# Valve_transistors.net
KiCad netlist of a schematic drawn in Altium Designer
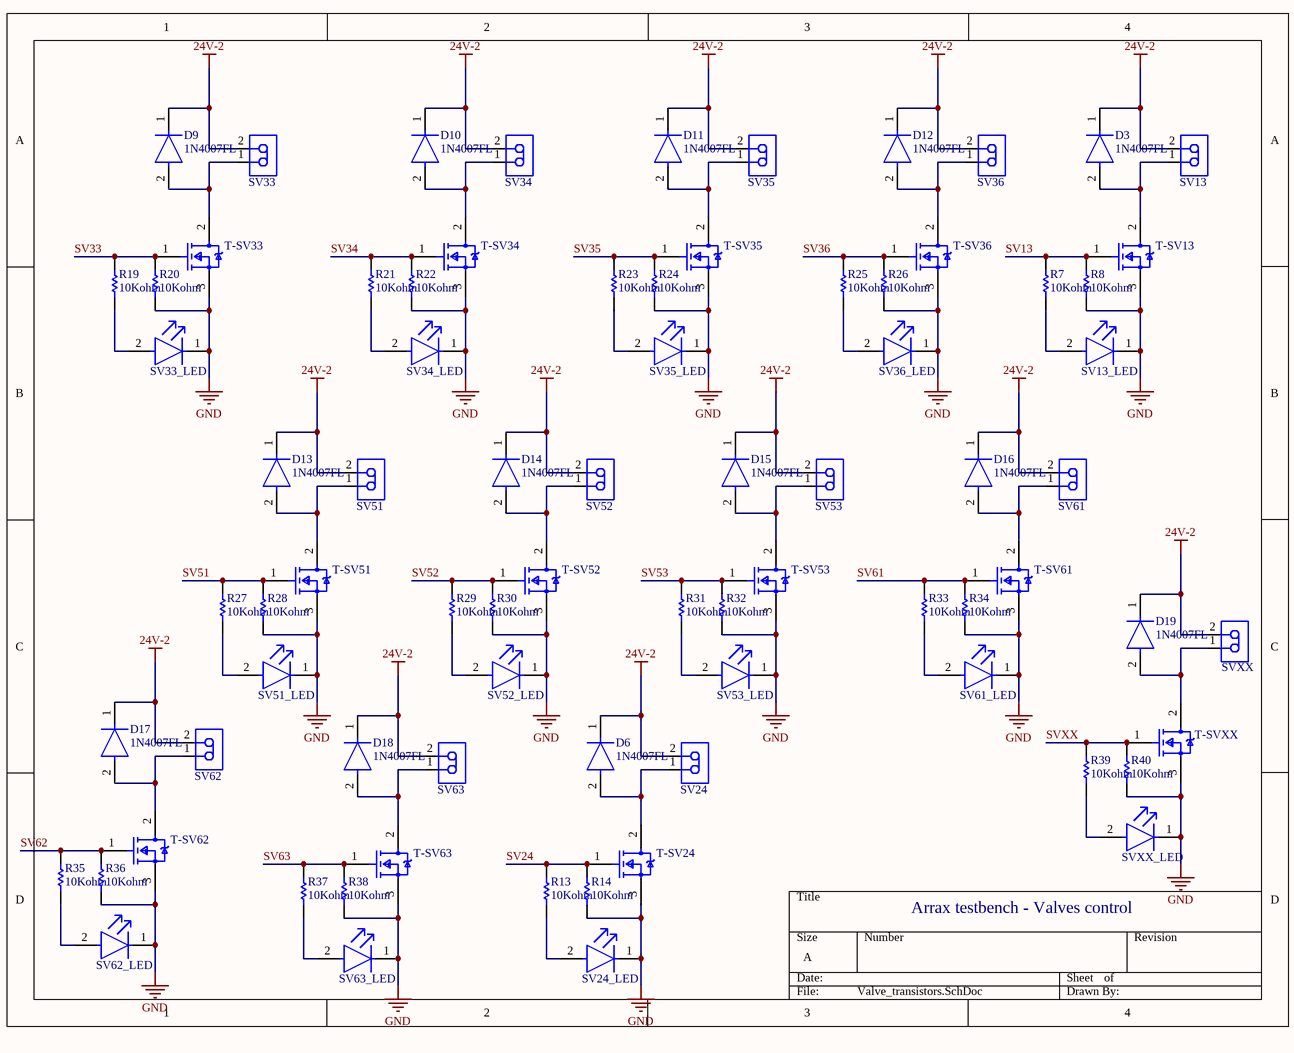
[diagram p0: Valve_transistors.SchDoc]

(export (version "E")
  (design (tool "Eeschema 10.0.6"))
  (components
    (comp (ref "D3")
      (value "1N4007FL")
      (footprint "FP-1N4007FL-MFG")
      (description "1N4007FL Diode Gen Purp 1KV 1A SOD123FL")
      (libsource (lib "Altium Content Vault") (part "d7152d700b627762746794eb795d46e"))
    )
    (comp (ref "D6")
      (value "1N4007FL")
      (footprint "FP-1N4007FL-MFG")
      (description "1N4007FL Diode Gen Purp 1KV 1A SOD123FL")
      (libsource (lib "Altium Content Vault") (part "d7152d700b627762746794eb795d46e"))
    )
    (comp (ref "D9")
      (value "1N4007FL")
      (footprint "FP-1N4007FL-MFG")
      (description "1N4007FL Diode Gen Purp 1KV 1A SOD123FL")
      (libsource (lib "Altium Content Vault") (part "d7152d700b627762746794eb795d46e"))
    )
    (comp (ref "D10")
      (value "1N4007FL")
      (footprint "FP-1N4007FL-MFG")
      (description "1N4007FL Diode Gen Purp 1KV 1A SOD123FL")
      (libsource (lib "Altium Content Vault") (part "d7152d700b627762746794eb795d46e"))
    )
    (comp (ref "D11")
      (value "1N4007FL")
      (footprint "FP-1N4007FL-MFG")
      (description "1N4007FL Diode Gen Purp 1KV 1A SOD123FL")
      (libsource (lib "Altium Content Vault") (part "d7152d700b627762746794eb795d46e"))
    )
    (comp (ref "D12")
      (value "1N4007FL")
      (footprint "FP-1N4007FL-MFG")
      (description "1N4007FL Diode Gen Purp 1KV 1A SOD123FL")
      (libsource (lib "Altium Content Vault") (part "d7152d700b627762746794eb795d46e"))
    )
    (comp (ref "D13")
      (value "1N4007FL")
      (footprint "FP-1N4007FL-MFG")
      (description "1N4007FL Diode Gen Purp 1KV 1A SOD123FL")
      (libsource (lib "Altium Content Vault") (part "d7152d700b627762746794eb795d46e"))
    )
    (comp (ref "D14")
      (value "1N4007FL")
      (footprint "FP-1N4007FL-MFG")
      (description "1N4007FL Diode Gen Purp 1KV 1A SOD123FL")
      (libsource (lib "Altium Content Vault") (part "d7152d700b627762746794eb795d46e"))
    )
    (comp (ref "D15")
      (value "1N4007FL")
      (footprint "FP-1N4007FL-MFG")
      (description "1N4007FL Diode Gen Purp 1KV 1A SOD123FL")
      (libsource (lib "Altium Content Vault") (part "d7152d700b627762746794eb795d46e"))
    )
    (comp (ref "D16")
      (value "1N4007FL")
      (footprint "FP-1N4007FL-MFG")
      (description "1N4007FL Diode Gen Purp 1KV 1A SOD123FL")
      (libsource (lib "Altium Content Vault") (part "d7152d700b627762746794eb795d46e"))
    )
    (comp (ref "D17")
      (value "1N4007FL")
      (footprint "FP-1N4007FL-MFG")
      (description "1N4007FL Diode Gen Purp 1KV 1A SOD123FL")
      (libsource (lib "Altium Content Vault") (part "d7152d700b627762746794eb795d46e"))
    )
    (comp (ref "D18")
      (value "1N4007FL")
      (footprint "FP-1N4007FL-MFG")
      (description "1N4007FL Diode Gen Purp 1KV 1A SOD123FL")
      (libsource (lib "Altium Content Vault") (part "d7152d700b627762746794eb795d46e"))
    )
    (comp (ref "D19")
      (value "1N4007FL")
      (footprint "FP-1N4007FL-MFG")
      (description "1N4007FL Diode Gen Purp 1KV 1A SOD123FL")
      (libsource (lib "Altium Content Vault") (part "d7152d700b627762746794eb795d46e"))
    )
    (comp (ref "R7")
      (value "10Kohm")
      (footprint "RESC2013X60X30NL20T20")
      (fields (field (name "MANUFACTURER") "KOA Speer") (field (name "PART NUMBER") "RK73H2ATTD1003F"))
      (libsource (lib "Altium Content Vault") (part "RES"))
    )
    (comp (ref "R8")
      (value "10Kohm")
      (footprint "RESC2013X60X30NL20T20")
      (fields (field (name "MANUFACTURER") "KOA Speer") (field (name "PART NUMBER") "RK73H2ATTD1003F"))
      (libsource (lib "Altium Content Vault") (part "RES"))
    )
    (comp (ref "R13")
      (value "10Kohm")
      (footprint "RESC2013X60X30NL20T20")
      (fields (field (name "MANUFACTURER") "KOA Speer") (field (name "PART NUMBER") "RK73H2ATTD1003F"))
      (libsource (lib "Altium Content Vault") (part "RES"))
    )
    (comp (ref "R14")
      (value "10Kohm")
      (footprint "RESC2013X60X30NL20T20")
      (fields (field (name "MANUFACTURER") "KOA Speer") (field (name "PART NUMBER") "RK73H2ATTD1003F"))
      (libsource (lib "Altium Content Vault") (part "RES"))
    )
    (comp (ref "R19")
      (value "10Kohm")
      (footprint "RESC2013X60X30NL20T20")
      (fields (field (name "MANUFACTURER") "KOA Speer") (field (name "PART NUMBER") "RK73H2ATTD1003F"))
      (libsource (lib "Altium Content Vault") (part "RES"))
    )
    (comp (ref "R20")
      (value "10Kohm")
      (footprint "RESC2013X60X30NL20T20")
      (fields (field (name "MANUFACTURER") "KOA Speer") (field (name "PART NUMBER") "RK73H2ATTD1003F"))
      (libsource (lib "Altium Content Vault") (part "RES"))
    )
    (comp (ref "R21")
      (value "10Kohm")
      (footprint "RESC2013X60X30NL20T20")
      (fields (field (name "MANUFACTURER") "KOA Speer") (field (name "PART NUMBER") "RK73H2ATTD1003F"))
      (libsource (lib "Altium Content Vault") (part "RES"))
    )
    (comp (ref "R22")
      (value "10Kohm")
      (footprint "RESC2013X60X30NL20T20")
      (fields (field (name "MANUFACTURER") "KOA Speer") (field (name "PART NUMBER") "RK73H2ATTD1003F"))
      (libsource (lib "Altium Content Vault") (part "RES"))
    )
    (comp (ref "R23")
      (value "10Kohm")
      (footprint "RESC2013X60X30NL20T20")
      (fields (field (name "MANUFACTURER") "KOA Speer") (field (name "PART NUMBER") "RK73H2ATTD1003F"))
      (libsource (lib "Altium Content Vault") (part "RES"))
    )
    (comp (ref "R24")
      (value "10Kohm")
      (footprint "RESC2013X60X30NL20T20")
      (fields (field (name "MANUFACTURER") "KOA Speer") (field (name "PART NUMBER") "RK73H2ATTD1003F"))
      (libsource (lib "Altium Content Vault") (part "RES"))
    )
    (comp (ref "R25")
      (value "10Kohm")
      (footprint "RESC2013X60X30NL20T20")
      (fields (field (name "MANUFACTURER") "KOA Speer") (field (name "PART NUMBER") "RK73H2ATTD1003F"))
      (libsource (lib "Altium Content Vault") (part "RES"))
    )
    (comp (ref "R26")
      (value "10Kohm")
      (footprint "RESC2013X60X30NL20T20")
      (fields (field (name "MANUFACTURER") "KOA Speer") (field (name "PART NUMBER") "RK73H2ATTD1003F"))
      (libsource (lib "Altium Content Vault") (part "RES"))
    )
    (comp (ref "R27")
      (value "10Kohm")
      (footprint "RESC2013X60X30NL20T20")
      (fields (field (name "MANUFACTURER") "KOA Speer") (field (name "PART NUMBER") "RK73H2ATTD1003F"))
      (libsource (lib "Altium Content Vault") (part "RES"))
    )
    (comp (ref "R28")
      (value "10Kohm")
      (footprint "RESC2013X60X30NL20T20")
      (fields (field (name "MANUFACTURER") "KOA Speer") (field (name "PART NUMBER") "RK73H2ATTD1003F"))
      (libsource (lib "Altium Content Vault") (part "RES"))
    )
    (comp (ref "R29")
      (value "10Kohm")
      (footprint "RESC2013X60X30NL20T20")
      (fields (field (name "MANUFACTURER") "KOA Speer") (field (name "PART NUMBER") "RK73H2ATTD1003F"))
      (libsource (lib "Altium Content Vault") (part "RES"))
    )
    (comp (ref "R30")
      (value "10Kohm")
      (footprint "RESC2013X60X30NL20T20")
      (fields (field (name "MANUFACTURER") "KOA Speer") (field (name "PART NUMBER") "RK73H2ATTD1003F"))
      (libsource (lib "Altium Content Vault") (part "RES"))
    )
    (comp (ref "R31")
      (value "10Kohm")
      (footprint "RESC2013X60X30NL20T20")
      (fields (field (name "MANUFACTURER") "KOA Speer") (field (name "PART NUMBER") "RK73H2ATTD1003F"))
      (libsource (lib "Altium Content Vault") (part "RES"))
    )
    (comp (ref "R32")
      (value "10Kohm")
      (footprint "RESC2013X60X30NL20T20")
      (fields (field (name "MANUFACTURER") "KOA Speer") (field (name "PART NUMBER") "RK73H2ATTD1003F"))
      (libsource (lib "Altium Content Vault") (part "RES"))
    )
    (comp (ref "R33")
      (value "10Kohm")
      (footprint "RESC2013X60X30NL20T20")
      (fields (field (name "MANUFACTURER") "KOA Speer") (field (name "PART NUMBER") "RK73H2ATTD1003F"))
      (libsource (lib "Altium Content Vault") (part "RES"))
    )
    (comp (ref "R34")
      (value "10Kohm")
      (footprint "RESC2013X60X30NL20T20")
      (fields (field (name "MANUFACTURER") "KOA Speer") (field (name "PART NUMBER") "RK73H2ATTD1003F"))
      (libsource (lib "Altium Content Vault") (part "RES"))
    )
    (comp (ref "R35")
      (value "10Kohm")
      (footprint "RESC2013X60X30NL20T20")
      (fields (field (name "MANUFACTURER") "KOA Speer") (field (name "PART NUMBER") "RK73H2ATTD1003F"))
      (libsource (lib "Altium Content Vault") (part "RES"))
    )
    (comp (ref "R36")
      (value "10Kohm")
      (footprint "RESC2013X60X30NL20T20")
      (fields (field (name "MANUFACTURER") "KOA Speer") (field (name "PART NUMBER") "RK73H2ATTD1003F"))
      (libsource (lib "Altium Content Vault") (part "RES"))
    )
    (comp (ref "R37")
      (value "10Kohm")
      (footprint "RESC2013X60X30NL20T20")
      (fields (field (name "MANUFACTURER") "KOA Speer") (field (name "PART NUMBER") "RK73H2ATTD1003F"))
      (libsource (lib "Altium Content Vault") (part "RES"))
    )
    (comp (ref "R38")
      (value "10Kohm")
      (footprint "RESC2013X60X30NL20T20")
      (fields (field (name "MANUFACTURER") "KOA Speer") (field (name "PART NUMBER") "RK73H2ATTD1003F"))
      (libsource (lib "Altium Content Vault") (part "RES"))
    )
    (comp (ref "R39")
      (value "10Kohm")
      (footprint "RESC2013X60X30NL20T20")
      (fields (field (name "MANUFACTURER") "KOA Speer") (field (name "PART NUMBER") "RK73H2ATTD1003F"))
      (libsource (lib "Altium Content Vault") (part "RES"))
    )
    (comp (ref "R40")
      (value "10Kohm")
      (footprint "RESC2013X60X30NL20T20")
      (fields (field (name "MANUFACTURER") "KOA Speer") (field (name "PART NUMBER") "RK73H2ATTD1003F"))
      (libsource (lib "Altium Content Vault") (part "RES"))
    )
    (comp (ref "SV13")
      (value "640456-2")
      (footprint "TECO-640456-2_V")
      (fields (field (name "MANUFACTURER") "TE Connectivity"))
      (libsource (lib "Altium Content Vault") (part "CN-2P-F-QF2"))
    )
    (comp (ref "SV13_LED")
      (value "LS R976-NR-1")
      (footprint "FP-LS_R976-MFG")
      (description "LED RED DIFFUSED 0805 SMD")
      (libsource (lib "Altium Content Vault") (part "8706943c75ba83719d021d2fdc84c58"))
    )
    (comp (ref "SV24")
      (value "640456-2")
      (footprint "TECO-640456-2_V")
      (fields (field (name "MANUFACTURER") "TE Connectivity"))
      (libsource (lib "Altium Content Vault") (part "CN-2P-F-QF2"))
    )
    (comp (ref "SV24_LED")
      (value "LS R976-NR-1")
      (footprint "FP-LS_R976-MFG")
      (description "LED RED DIFFUSED 0805 SMD")
      (libsource (lib "Altium Content Vault") (part "8706943c75ba83719d021d2fdc84c58"))
    )
    (comp (ref "SV33")
      (value "640456-2")
      (footprint "TECO-640456-2_V")
      (fields (field (name "MANUFACTURER") "TE Connectivity"))
      (libsource (lib "Altium Content Vault") (part "CN-2P-F-QF2"))
    )
    (comp (ref "SV33_LED")
      (value "LS R976-NR-1")
      (footprint "FP-LS_R976-MFG")
      (description "LED RED DIFFUSED 0805 SMD")
      (libsource (lib "Altium Content Vault") (part "8706943c75ba83719d021d2fdc84c58"))
    )
    (comp (ref "SV34")
      (value "640456-2")
      (footprint "TECO-640456-2_V")
      (fields (field (name "MANUFACTURER") "TE Connectivity"))
      (libsource (lib "Altium Content Vault") (part "CN-2P-F-QF2"))
    )
    (comp (ref "SV34_LED")
      (value "LS R976-NR-1")
      (footprint "FP-LS_R976-MFG")
      (description "LED RED DIFFUSED 0805 SMD")
      (libsource (lib "Altium Content Vault") (part "8706943c75ba83719d021d2fdc84c58"))
    )
    (comp (ref "SV35")
      (value "640456-2")
      (footprint "TECO-640456-2_V")
      (fields (field (name "MANUFACTURER") "TE Connectivity"))
      (libsource (lib "Altium Content Vault") (part "CN-2P-F-QF2"))
    )
    (comp (ref "SV35_LED")
      (value "LS R976-NR-1")
      (footprint "FP-LS_R976-MFG")
      (description "LED RED DIFFUSED 0805 SMD")
      (libsource (lib "Altium Content Vault") (part "8706943c75ba83719d021d2fdc84c58"))
    )
    (comp (ref "SV36")
      (value "640456-2")
      (footprint "TECO-640456-2_V")
      (fields (field (name "MANUFACTURER") "TE Connectivity"))
      (libsource (lib "Altium Content Vault") (part "CN-2P-F-QF2"))
    )
    (comp (ref "SV36_LED")
      (value "LS R976-NR-1")
      (footprint "FP-LS_R976-MFG")
      (description "LED RED DIFFUSED 0805 SMD")
      (libsource (lib "Altium Content Vault") (part "8706943c75ba83719d021d2fdc84c58"))
    )
    (comp (ref "SV51")
      (value "640456-2")
      (footprint "TECO-640456-2_V")
      (fields (field (name "MANUFACTURER") "TE Connectivity"))
      (libsource (lib "Altium Content Vault") (part "CN-2P-F-QF2"))
    )
    (comp (ref "SV51_LED")
      (value "LS R976-NR-1")
      (footprint "FP-LS_R976-MFG")
      (description "LED RED DIFFUSED 0805 SMD")
      (libsource (lib "Altium Content Vault") (part "8706943c75ba83719d021d2fdc84c58"))
    )
    (comp (ref "SV52")
      (value "640456-2")
      (footprint "TECO-640456-2_V")
      (fields (field (name "MANUFACTURER") "TE Connectivity"))
      (libsource (lib "Altium Content Vault") (part "CN-2P-F-QF2"))
    )
    (comp (ref "SV52_LED")
      (value "LS R976-NR-1")
      (footprint "FP-LS_R976-MFG")
      (description "LED RED DIFFUSED 0805 SMD")
      (libsource (lib "Altium Content Vault") (part "8706943c75ba83719d021d2fdc84c58"))
    )
    (comp (ref "SV53")
      (value "640456-2")
      (footprint "TECO-640456-2_V")
      (fields (field (name "MANUFACTURER") "TE Connectivity"))
      (libsource (lib "Altium Content Vault") (part "CN-2P-F-QF2"))
    )
    (comp (ref "SV53_LED")
      (value "LS R976-NR-1")
      (footprint "FP-LS_R976-MFG")
      (description "LED RED DIFFUSED 0805 SMD")
      (libsource (lib "Altium Content Vault") (part "8706943c75ba83719d021d2fdc84c58"))
    )
    (comp (ref "SV61")
      (value "640456-2")
      (footprint "TECO-640456-2_V")
      (fields (field (name "MANUFACTURER") "TE Connectivity"))
      (libsource (lib "Altium Content Vault") (part "CN-2P-F-QF2"))
    )
    (comp (ref "SV61_LED")
      (value "LS R976-NR-1")
      (footprint "FP-LS_R976-MFG")
      (description "LED RED DIFFUSED 0805 SMD")
      (libsource (lib "Altium Content Vault") (part "8706943c75ba83719d021d2fdc84c58"))
    )
    (comp (ref "SV62")
      (value "640456-2")
      (footprint "TECO-640456-2_V")
      (fields (field (name "MANUFACTURER") "TE Connectivity"))
      (libsource (lib "Altium Content Vault") (part "CN-2P-F-QF2"))
    )
    (comp (ref "SV62_LED")
      (value "LS R976-NR-1")
      (footprint "FP-LS_R976-MFG")
      (description "LED RED DIFFUSED 0805 SMD")
      (libsource (lib "Altium Content Vault") (part "8706943c75ba83719d021d2fdc84c58"))
    )
    (comp (ref "SV63")
      (value "640456-2")
      (footprint "TECO-640456-2_V")
      (fields (field (name "MANUFACTURER") "TE Connectivity"))
      (libsource (lib "Altium Content Vault") (part "CN-2P-F-QF2"))
    )
    (comp (ref "SV63_LED")
      (value "LS R976-NR-1")
      (footprint "FP-LS_R976-MFG")
      (description "LED RED DIFFUSED 0805 SMD")
      (libsource (lib "Altium Content Vault") (part "8706943c75ba83719d021d2fdc84c58"))
    )
    (comp (ref "SVXX")
      (value "640456-2")
      (footprint "TECO-640456-2_V")
      (fields (field (name "MANUFACTURER") "TE Connectivity"))
      (libsource (lib "Altium Content Vault") (part "CN-2P-F-QF2"))
    )
    (comp (ref "SVXX_LED")
      (value "LS R976-NR-1")
      (footprint "FP-LS_R976-MFG")
      (description "LED RED DIFFUSED 0805 SMD")
      (libsource (lib "Altium Content Vault") (part "8706943c75ba83719d021d2fdc84c58"))
    )
    (comp (ref "T-SV13")
      (value "IRLZ44NPbF")
      (footprint "FP-PG-TO220-3-MFG")
      (description "MOSFET N-CH 55V 47A TO220AB")
      (libsource (lib "Altium Content Vault") (part "b09f7f152735e370c1ea22a33fa83d6"))
    )
    (comp (ref "T-SV24")
      (value "IRLZ44NPbF")
      (footprint "FP-PG-TO220-3-MFG")
      (description "MOSFET N-CH 55V 47A TO220AB")
      (libsource (lib "Altium Content Vault") (part "b09f7f152735e370c1ea22a33fa83d6"))
    )
    (comp (ref "T-SV33")
      (value "IRLZ44NPbF")
      (footprint "FP-PG-TO220-3-MFG")
      (description "MOSFET N-CH 55V 47A TO220AB")
      (libsource (lib "Altium Content Vault") (part "b09f7f152735e370c1ea22a33fa83d6"))
    )
    (comp (ref "T-SV34")
      (value "IRLZ44NPbF")
      (footprint "FP-PG-TO220-3-MFG")
      (description "MOSFET N-CH 55V 47A TO220AB")
      (libsource (lib "Altium Content Vault") (part "b09f7f152735e370c1ea22a33fa83d6"))
    )
    (comp (ref "T-SV35")
      (value "IRLZ44NPbF")
      (footprint "FP-PG-TO220-3-MFG")
      (description "MOSFET N-CH 55V 47A TO220AB")
      (libsource (lib "Altium Content Vault") (part "b09f7f152735e370c1ea22a33fa83d6"))
    )
    (comp (ref "T-SV36")
      (value "IRLZ44NPbF")
      (footprint "FP-PG-TO220-3-MFG")
      (description "MOSFET N-CH 55V 47A TO220AB")
      (libsource (lib "Altium Content Vault") (part "b09f7f152735e370c1ea22a33fa83d6"))
    )
    (comp (ref "T-SV51")
      (value "IRLZ44NPbF")
      (footprint "FP-PG-TO220-3-MFG")
      (description "MOSFET N-CH 55V 47A TO220AB")
      (libsource (lib "Altium Content Vault") (part "b09f7f152735e370c1ea22a33fa83d6"))
    )
    (comp (ref "T-SV52")
      (value "IRLZ44NPbF")
      (footprint "FP-PG-TO220-3-MFG")
      (description "MOSFET N-CH 55V 47A TO220AB")
      (libsource (lib "Altium Content Vault") (part "b09f7f152735e370c1ea22a33fa83d6"))
    )
    (comp (ref "T-SV53")
      (value "IRLZ44NPbF")
      (footprint "FP-PG-TO220-3-MFG")
      (description "MOSFET N-CH 55V 47A TO220AB")
      (libsource (lib "Altium Content Vault") (part "b09f7f152735e370c1ea22a33fa83d6"))
    )
    (comp (ref "T-SV61")
      (value "IRLZ44NPbF")
      (footprint "FP-PG-TO220-3-MFG")
      (description "MOSFET N-CH 55V 47A TO220AB")
      (libsource (lib "Altium Content Vault") (part "b09f7f152735e370c1ea22a33fa83d6"))
    )
    (comp (ref "T-SV62")
      (value "IRLZ44NPbF")
      (footprint "FP-PG-TO220-3-MFG")
      (description "MOSFET N-CH 55V 47A TO220AB")
      (libsource (lib "Altium Content Vault") (part "b09f7f152735e370c1ea22a33fa83d6"))
    )
    (comp (ref "T-SV63")
      (value "IRLZ44NPbF")
      (footprint "FP-PG-TO220-3-MFG")
      (description "MOSFET N-CH 55V 47A TO220AB")
      (libsource (lib "Altium Content Vault") (part "b09f7f152735e370c1ea22a33fa83d6"))
    )
    (comp (ref "T-SVXX")
      (value "IRLZ44NPbF")
      (footprint "FP-PG-TO220-3-MFG")
      (description "MOSFET N-CH 55V 47A TO220AB")
      (libsource (lib "Altium Content Vault") (part "b09f7f152735e370c1ea22a33fa83d6"))
    )
  )
  (nets
    (net (code "1") (name "/SV13") (class "Default")
      (node (ref "R7") (pin "2") (pinfunction "2_2") (pintype "passive"))
      (node (ref "R8") (pin "2") (pinfunction "2_2") (pintype "passive"))
      (node (ref "T-SV13") (pin "1") (pinfunction "G_1") (pintype "passive"))
    )
    (net (code "2") (name "/SV24") (class "Default")
      (node (ref "R13") (pin "2") (pinfunction "2_2") (pintype "passive"))
      (node (ref "R14") (pin "2") (pinfunction "2_2") (pintype "passive"))
      (node (ref "T-SV24") (pin "1") (pinfunction "G_1") (pintype "passive"))
    )
    (net (code "3") (name "/SV33") (class "Default")
      (node (ref "R19") (pin "2") (pinfunction "2_2") (pintype "passive"))
      (node (ref "R20") (pin "2") (pinfunction "2_2") (pintype "passive"))
      (node (ref "T-SV33") (pin "1") (pinfunction "G_1") (pintype "passive"))
    )
    (net (code "4") (name "/SV34") (class "Default")
      (node (ref "R21") (pin "2") (pinfunction "2_2") (pintype "passive"))
      (node (ref "R22") (pin "2") (pinfunction "2_2") (pintype "passive"))
      (node (ref "T-SV34") (pin "1") (pinfunction "G_1") (pintype "passive"))
    )
    (net (code "5") (name "/SV35") (class "Default")
      (node (ref "R23") (pin "2") (pinfunction "2_2") (pintype "passive"))
      (node (ref "R24") (pin "2") (pinfunction "2_2") (pintype "passive"))
      (node (ref "T-SV35") (pin "1") (pinfunction "G_1") (pintype "passive"))
    )
    (net (code "6") (name "/SV36") (class "Default")
      (node (ref "R25") (pin "2") (pinfunction "2_2") (pintype "passive"))
      (node (ref "R26") (pin "2") (pinfunction "2_2") (pintype "passive"))
      (node (ref "T-SV36") (pin "1") (pinfunction "G_1") (pintype "passive"))
    )
    (net (code "7") (name "/SV51") (class "Default")
      (node (ref "R27") (pin "2") (pinfunction "2_2") (pintype "passive"))
      (node (ref "R28") (pin "2") (pinfunction "2_2") (pintype "passive"))
      (node (ref "T-SV51") (pin "1") (pinfunction "G_1") (pintype "passive"))
    )
    (net (code "8") (name "/SV52") (class "Default")
      (node (ref "R29") (pin "2") (pinfunction "2_2") (pintype "passive"))
      (node (ref "R30") (pin "2") (pinfunction "2_2") (pintype "passive"))
      (node (ref "T-SV52") (pin "1") (pinfunction "G_1") (pintype "passive"))
    )
    (net (code "9") (name "/SV53") (class "Default")
      (node (ref "R31") (pin "2") (pinfunction "2_2") (pintype "passive"))
      (node (ref "R32") (pin "2") (pinfunction "2_2") (pintype "passive"))
      (node (ref "T-SV53") (pin "1") (pinfunction "G_1") (pintype "passive"))
    )
    (net (code "10") (name "/SV61") (class "Default")
      (node (ref "R33") (pin "2") (pinfunction "2_2") (pintype "passive"))
      (node (ref "R34") (pin "2") (pinfunction "2_2") (pintype "passive"))
      (node (ref "T-SV61") (pin "1") (pinfunction "G_1") (pintype "passive"))
    )
    (net (code "11") (name "/SV62") (class "Default")
      (node (ref "R35") (pin "2") (pinfunction "2_2") (pintype "passive"))
      (node (ref "R36") (pin "2") (pinfunction "2_2") (pintype "passive"))
      (node (ref "T-SV62") (pin "1") (pinfunction "G_1") (pintype "passive"))
    )
    (net (code "12") (name "/SV63") (class "Default")
      (node (ref "R37") (pin "2") (pinfunction "2_2") (pintype "passive"))
      (node (ref "R38") (pin "2") (pinfunction "2_2") (pintype "passive"))
      (node (ref "T-SV63") (pin "1") (pinfunction "G_1") (pintype "passive"))
    )
    (net (code "13") (name "/SVXX") (class "Default")
      (node (ref "R39") (pin "2") (pinfunction "2_2") (pintype "passive"))
      (node (ref "R40") (pin "2") (pinfunction "2_2") (pintype "passive"))
      (node (ref "T-SVXX") (pin "1") (pinfunction "G_1") (pintype "passive"))
    )
    (net (code "14") (name "24V-2") (class "Default")
      (node (ref "D10") (pin "1") (pinfunction "C_1") (pintype "passive"))
      (node (ref "D11") (pin "1") (pinfunction "C_1") (pintype "passive"))
      (node (ref "D12") (pin "1") (pinfunction "C_1") (pintype "passive"))
      (node (ref "D13") (pin "1") (pinfunction "C_1") (pintype "passive"))
      (node (ref "D14") (pin "1") (pinfunction "C_1") (pintype "passive"))
      (node (ref "D15") (pin "1") (pinfunction "C_1") (pintype "passive"))
      (node (ref "D16") (pin "1") (pinfunction "C_1") (pintype "passive"))
      (node (ref "D17") (pin "1") (pinfunction "C_1") (pintype "passive"))
      (node (ref "D18") (pin "1") (pinfunction "C_1") (pintype "passive"))
      (node (ref "D19") (pin "1") (pinfunction "C_1") (pintype "passive"))
      (node (ref "D3") (pin "1") (pinfunction "C_1") (pintype "passive"))
      (node (ref "D6") (pin "1") (pinfunction "C_1") (pintype "passive"))
      (node (ref "D9") (pin "1") (pinfunction "C_1") (pintype "passive"))
      (node (ref "SV13") (pin "2") (pinfunction "2_2") (pintype "passive"))
      (node (ref "SV24") (pin "2") (pinfunction "2_2") (pintype "passive"))
      (node (ref "SV33") (pin "2") (pinfunction "2_2") (pintype "passive"))
      (node (ref "SV34") (pin "2") (pinfunction "2_2") (pintype "passive"))
      (node (ref "SV35") (pin "2") (pinfunction "2_2") (pintype "passive"))
      (node (ref "SV36") (pin "2") (pinfunction "2_2") (pintype "passive"))
      (node (ref "SV51") (pin "2") (pinfunction "2_2") (pintype "passive"))
      (node (ref "SV52") (pin "2") (pinfunction "2_2") (pintype "passive"))
      (node (ref "SV53") (pin "2") (pinfunction "2_2") (pintype "passive"))
      (node (ref "SV61") (pin "2") (pinfunction "2_2") (pintype "passive"))
      (node (ref "SV62") (pin "2") (pinfunction "2_2") (pintype "passive"))
      (node (ref "SV63") (pin "2") (pinfunction "2_2") (pintype "passive"))
      (node (ref "SVXX") (pin "2") (pinfunction "2_2") (pintype "passive"))
    )
    (net (code "15") (name "GND") (class "Default")
      (node (ref "R14") (pin "1") (pinfunction "1_1") (pintype "passive"))
      (node (ref "R20") (pin "1") (pinfunction "1_1") (pintype "passive"))
      (node (ref "R22") (pin "1") (pinfunction "1_1") (pintype "passive"))
      (node (ref "R24") (pin "1") (pinfunction "1_1") (pintype "passive"))
      (node (ref "R26") (pin "1") (pinfunction "1_1") (pintype "passive"))
      (node (ref "R28") (pin "1") (pinfunction "1_1") (pintype "passive"))
      (node (ref "R30") (pin "1") (pinfunction "1_1") (pintype "passive"))
      (node (ref "R32") (pin "1") (pinfunction "1_1") (pintype "passive"))
      (node (ref "R34") (pin "1") (pinfunction "1_1") (pintype "passive"))
      (node (ref "R36") (pin "1") (pinfunction "1_1") (pintype "passive"))
      (node (ref "R38") (pin "1") (pinfunction "1_1") (pintype "passive"))
      (node (ref "R40") (pin "1") (pinfunction "1_1") (pintype "passive"))
      (node (ref "R8") (pin "1") (pinfunction "1_1") (pintype "passive"))
      (node (ref "SV13_LED") (pin "1") (pinfunction "C_1") (pintype "passive"))
      (node (ref "SV24_LED") (pin "1") (pinfunction "C_1") (pintype "passive"))
      (node (ref "SV33_LED") (pin "1") (pinfunction "C_1") (pintype "passive"))
      (node (ref "SV34_LED") (pin "1") (pinfunction "C_1") (pintype "passive"))
      (node (ref "SV35_LED") (pin "1") (pinfunction "C_1") (pintype "passive"))
      (node (ref "SV36_LED") (pin "1") (pinfunction "C_1") (pintype "passive"))
      (node (ref "SV51_LED") (pin "1") (pinfunction "C_1") (pintype "passive"))
      (node (ref "SV52_LED") (pin "1") (pinfunction "C_1") (pintype "passive"))
      (node (ref "SV53_LED") (pin "1") (pinfunction "C_1") (pintype "passive"))
      (node (ref "SV61_LED") (pin "1") (pinfunction "C_1") (pintype "passive"))
      (node (ref "SV62_LED") (pin "1") (pinfunction "C_1") (pintype "passive"))
      (node (ref "SV63_LED") (pin "1") (pinfunction "C_1") (pintype "passive"))
      (node (ref "SVXX_LED") (pin "1") (pinfunction "C_1") (pintype "passive"))
      (node (ref "T-SV13") (pin "3") (pinfunction "S_3") (pintype "passive"))
      (node (ref "T-SV24") (pin "3") (pinfunction "S_3") (pintype "passive"))
      (node (ref "T-SV33") (pin "3") (pinfunction "S_3") (pintype "passive"))
      (node (ref "T-SV34") (pin "3") (pinfunction "S_3") (pintype "passive"))
      (node (ref "T-SV35") (pin "3") (pinfunction "S_3") (pintype "passive"))
      (node (ref "T-SV36") (pin "3") (pinfunction "S_3") (pintype "passive"))
      (node (ref "T-SV51") (pin "3") (pinfunction "S_3") (pintype "passive"))
      (node (ref "T-SV52") (pin "3") (pinfunction "S_3") (pintype "passive"))
      (node (ref "T-SV53") (pin "3") (pinfunction "S_3") (pintype "passive"))
      (node (ref "T-SV61") (pin "3") (pinfunction "S_3") (pintype "passive"))
      (node (ref "T-SV62") (pin "3") (pinfunction "S_3") (pintype "passive"))
      (node (ref "T-SV63") (pin "3") (pinfunction "S_3") (pintype "passive"))
      (node (ref "T-SVXX") (pin "3") (pinfunction "S_3") (pintype "passive"))
    )
    (net (code "16") (name "Net-(D3-A)") (class "Default")
      (node (ref "D3") (pin "2") (pinfunction "A_2") (pintype "passive"))
      (node (ref "SV13") (pin "1") (pinfunction "1_1") (pintype "passive"))
      (node (ref "T-SV13") (pin "2") (pinfunction "D_2") (pintype "passive"))
    )
    (net (code "17") (name "Net-(D6-A)") (class "Default")
      (node (ref "D6") (pin "2") (pinfunction "A_2") (pintype "passive"))
      (node (ref "SV24") (pin "1") (pinfunction "1_1") (pintype "passive"))
      (node (ref "T-SV24") (pin "2") (pinfunction "D_2") (pintype "passive"))
    )
    (net (code "18") (name "Net-(D9-A)") (class "Default")
      (node (ref "D9") (pin "2") (pinfunction "A_2") (pintype "passive"))
      (node (ref "SV33") (pin "1") (pinfunction "1_1") (pintype "passive"))
      (node (ref "T-SV33") (pin "2") (pinfunction "D_2") (pintype "passive"))
    )
    (net (code "19") (name "Net-(D10-A)") (class "Default")
      (node (ref "D10") (pin "2") (pinfunction "A_2") (pintype "passive"))
      (node (ref "SV34") (pin "1") (pinfunction "1_1") (pintype "passive"))
      (node (ref "T-SV34") (pin "2") (pinfunction "D_2") (pintype "passive"))
    )
    (net (code "20") (name "Net-(D11-A)") (class "Default")
      (node (ref "D11") (pin "2") (pinfunction "A_2") (pintype "passive"))
      (node (ref "SV35") (pin "1") (pinfunction "1_1") (pintype "passive"))
      (node (ref "T-SV35") (pin "2") (pinfunction "D_2") (pintype "passive"))
    )
    (net (code "21") (name "Net-(D12-A)") (class "Default")
      (node (ref "D12") (pin "2") (pinfunction "A_2") (pintype "passive"))
      (node (ref "SV36") (pin "1") (pinfunction "1_1") (pintype "passive"))
      (node (ref "T-SV36") (pin "2") (pinfunction "D_2") (pintype "passive"))
    )
    (net (code "22") (name "Net-(D13-A)") (class "Default")
      (node (ref "D13") (pin "2") (pinfunction "A_2") (pintype "passive"))
      (node (ref "SV51") (pin "1") (pinfunction "1_1") (pintype "passive"))
      (node (ref "T-SV51") (pin "2") (pinfunction "D_2") (pintype "passive"))
    )
    (net (code "23") (name "Net-(D14-A)") (class "Default")
      (node (ref "D14") (pin "2") (pinfunction "A_2") (pintype "passive"))
      (node (ref "SV52") (pin "1") (pinfunction "1_1") (pintype "passive"))
      (node (ref "T-SV52") (pin "2") (pinfunction "D_2") (pintype "passive"))
    )
    (net (code "24") (name "Net-(D15-A)") (class "Default")
      (node (ref "D15") (pin "2") (pinfunction "A_2") (pintype "passive"))
      (node (ref "SV53") (pin "1") (pinfunction "1_1") (pintype "passive"))
      (node (ref "T-SV53") (pin "2") (pinfunction "D_2") (pintype "passive"))
    )
    (net (code "25") (name "Net-(D16-A)") (class "Default")
      (node (ref "D16") (pin "2") (pinfunction "A_2") (pintype "passive"))
      (node (ref "SV61") (pin "1") (pinfunction "1_1") (pintype "passive"))
      (node (ref "T-SV61") (pin "2") (pinfunction "D_2") (pintype "passive"))
    )
    (net (code "26") (name "Net-(D17-A)") (class "Default")
      (node (ref "D17") (pin "2") (pinfunction "A_2") (pintype "passive"))
      (node (ref "SV62") (pin "1") (pinfunction "1_1") (pintype "passive"))
      (node (ref "T-SV62") (pin "2") (pinfunction "D_2") (pintype "passive"))
    )
    (net (code "27") (name "Net-(D18-A)") (class "Default")
      (node (ref "D18") (pin "2") (pinfunction "A_2") (pintype "passive"))
      (node (ref "SV63") (pin "1") (pinfunction "1_1") (pintype "passive"))
      (node (ref "T-SV63") (pin "2") (pinfunction "D_2") (pintype "passive"))
    )
    (net (code "28") (name "Net-(D19-A)") (class "Default")
      (node (ref "D19") (pin "2") (pinfunction "A_2") (pintype "passive"))
      (node (ref "SVXX") (pin "1") (pinfunction "1_1") (pintype "passive"))
      (node (ref "T-SVXX") (pin "2") (pinfunction "D_2") (pintype "passive"))
    )
    (net (code "29") (name "Net-(SV13_LED-A)") (class "Default")
      (node (ref "R7") (pin "1") (pinfunction "1_1") (pintype "passive"))
      (node (ref "SV13_LED") (pin "2") (pinfunction "A_2") (pintype "passive"))
    )
    (net (code "30") (name "Net-(SV24_LED-A)") (class "Default")
      (node (ref "R13") (pin "1") (pinfunction "1_1") (pintype "passive"))
      (node (ref "SV24_LED") (pin "2") (pinfunction "A_2") (pintype "passive"))
    )
    (net (code "31") (name "Net-(SV33_LED-A)") (class "Default")
      (node (ref "R19") (pin "1") (pinfunction "1_1") (pintype "passive"))
      (node (ref "SV33_LED") (pin "2") (pinfunction "A_2") (pintype "passive"))
    )
    (net (code "32") (name "Net-(SV34_LED-A)") (class "Default")
      (node (ref "R21") (pin "1") (pinfunction "1_1") (pintype "passive"))
      (node (ref "SV34_LED") (pin "2") (pinfunction "A_2") (pintype "passive"))
    )
    (net (code "33") (name "Net-(SV35_LED-A)") (class "Default")
      (node (ref "R23") (pin "1") (pinfunction "1_1") (pintype "passive"))
      (node (ref "SV35_LED") (pin "2") (pinfunction "A_2") (pintype "passive"))
    )
    (net (code "34") (name "Net-(SV36_LED-A)") (class "Default")
      (node (ref "R25") (pin "1") (pinfunction "1_1") (pintype "passive"))
      (node (ref "SV36_LED") (pin "2") (pinfunction "A_2") (pintype "passive"))
    )
    (net (code "35") (name "Net-(SV51_LED-A)") (class "Default")
      (node (ref "R27") (pin "1") (pinfunction "1_1") (pintype "passive"))
      (node (ref "SV51_LED") (pin "2") (pinfunction "A_2") (pintype "passive"))
    )
    (net (code "36") (name "Net-(SV52_LED-A)") (class "Default")
      (node (ref "R29") (pin "1") (pinfunction "1_1") (pintype "passive"))
      (node (ref "SV52_LED") (pin "2") (pinfunction "A_2") (pintype "passive"))
    )
    (net (code "37") (name "Net-(SV53_LED-A)") (class "Default")
      (node (ref "R31") (pin "1") (pinfunction "1_1") (pintype "passive"))
      (node (ref "SV53_LED") (pin "2") (pinfunction "A_2") (pintype "passive"))
    )
    (net (code "38") (name "Net-(SV61_LED-A)") (class "Default")
      (node (ref "R33") (pin "1") (pinfunction "1_1") (pintype "passive"))
      (node (ref "SV61_LED") (pin "2") (pinfunction "A_2") (pintype "passive"))
    )
    (net (code "39") (name "Net-(SV62_LED-A)") (class "Default")
      (node (ref "R35") (pin "1") (pinfunction "1_1") (pintype "passive"))
      (node (ref "SV62_LED") (pin "2") (pinfunction "A_2") (pintype "passive"))
    )
    (net (code "40") (name "Net-(SV63_LED-A)") (class "Default")
      (node (ref "R37") (pin "1") (pinfunction "1_1") (pintype "passive"))
      (node (ref "SV63_LED") (pin "2") (pinfunction "A_2") (pintype "passive"))
    )
    (net (code "41") (name "Net-(SVXX_LED-A)") (class "Default")
      (node (ref "R39") (pin "1") (pinfunction "1_1") (pintype "passive"))
      (node (ref "SVXX_LED") (pin "2") (pinfunction "A_2") (pintype "passive"))
    )
  )
)
